# RAM.net
KiCad netlist of a schematic drawn in Altium Designer
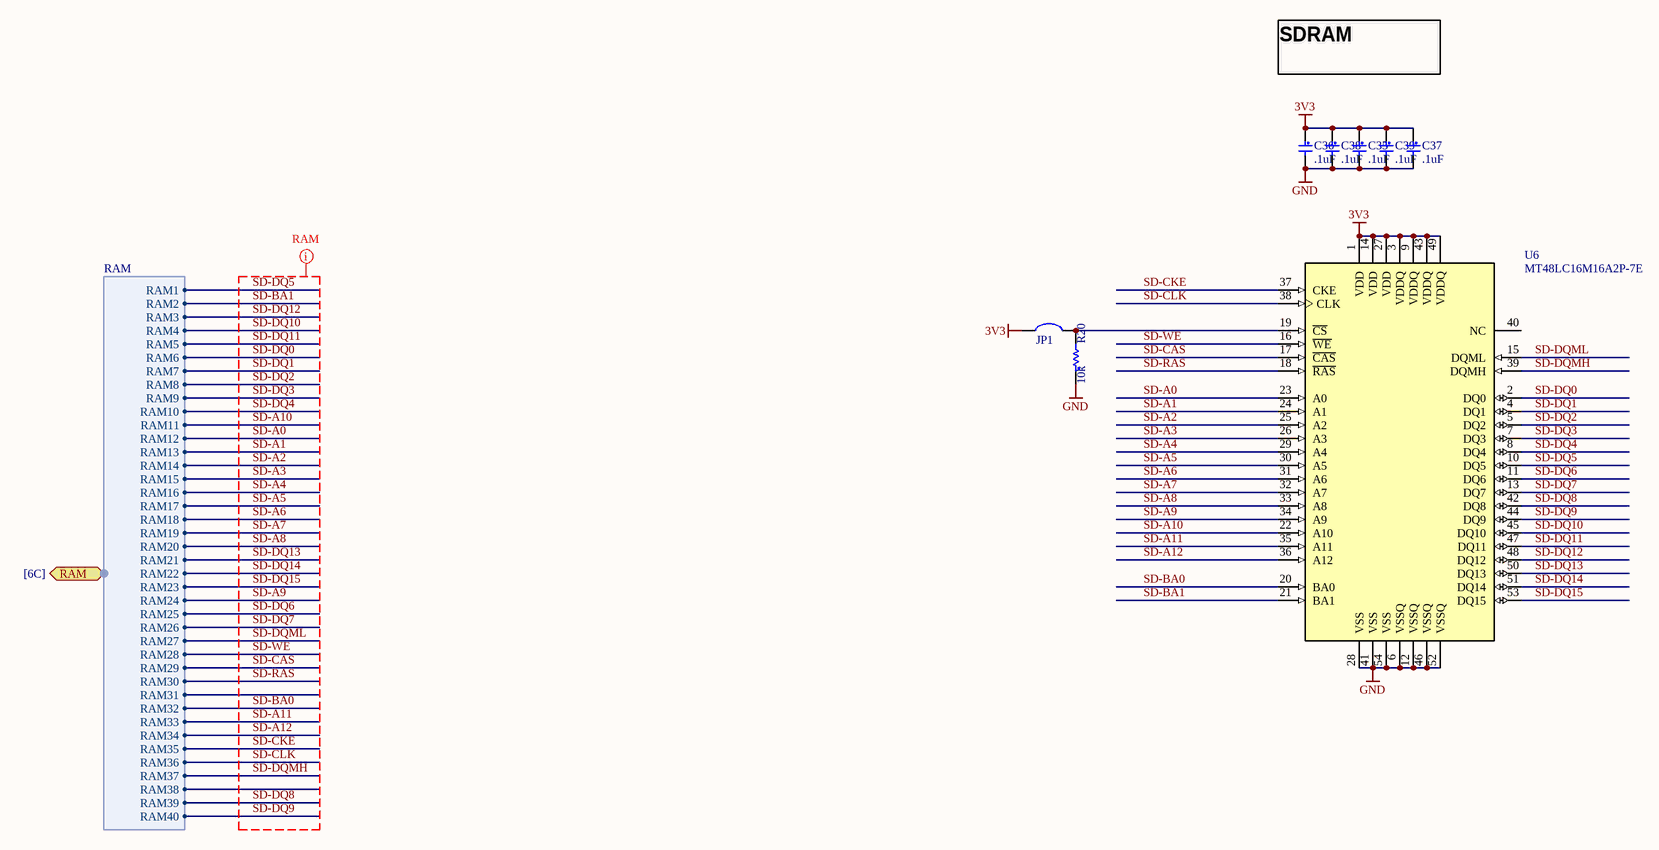
[diagram p0: RAM.SchDoc]

(export (version "E")
  (design (tool "Eeschema 10.0.6"))
  (components
    (comp (ref "C35")
      (value ".1uF")
      (description "CAP CER 0.1UF 25V Y5V 0603")
      (fields
        (field (name "MANUFACTURER") "Samsung Electro-Mechanics America, Inc")
        (field (name "MANUFACTURER PART NUMBER") "CL10F104ZA8NNNC")
      )
      (libsource (lib "mCapacitors") (part "C0603 - CL10F104ZA8NNNC"))
    )
    (comp (ref "C36")
      (value ".1uF")
      (description "CAP CER 0.1UF 25V Y5V 0603")
      (fields
        (field (name "MANUFACTURER") "Samsung Electro-Mechanics America, Inc")
        (field (name "MANUFACTURER PART NUMBER") "CL10F104ZA8NNNC")
      )
      (libsource (lib "mCapacitors") (part "C0603 - CL10F104ZA8NNNC"))
    )
    (comp (ref "C37")
      (value ".1uF")
      (description "CAP CER 0.1UF 25V Y5V 0603")
      (fields
        (field (name "MANUFACTURER") "Samsung Electro-Mechanics America, Inc")
        (field (name "MANUFACTURER PART NUMBER") "CL10F104ZA8NNNC")
      )
      (libsource (lib "mCapacitors") (part "C0603 - CL10F104ZA8NNNC"))
    )
    (comp (ref "C38")
      (value ".1uF")
      (description "CAP CER 0.1UF 25V Y5V 0603")
      (fields
        (field (name "MANUFACTURER") "Samsung Electro-Mechanics America, Inc")
        (field (name "MANUFACTURER PART NUMBER") "CL10F104ZA8NNNC")
      )
      (libsource (lib "mCapacitors") (part "C0603 - CL10F104ZA8NNNC"))
    )
    (comp (ref "C39")
      (value ".1uF")
      (description "CAP CER 0.1UF 25V Y5V 0603")
      (fields
        (field (name "MANUFACTURER") "Samsung Electro-Mechanics America, Inc")
        (field (name "MANUFACTURER PART NUMBER") "CL10F104ZA8NNNC")
      )
      (libsource (lib "mCapacitors") (part "C0603 - CL10F104ZA8NNNC"))
    )
    (comp (ref "JP1")
      (value "Solder Jumper")
      (footprint "SOLDER_JUMPER")
      (description "Solder/Configuration Jumper")
      (fields (field (name "MANUFACTURER") "n/a"))
      (libsource (lib "mConnector") (part "Solder Jumper"))
    )
    (comp (ref "R20")
      (value "10k")
      (footprint "mRCL:R0603")
      (description "10k Thick Film Resistors - SMD 1/10watt 10Kohms 1%")
      (fields
        (field (name "MANUFACTURER") "Vishay Dale")
        (field (name "MANUFACTURER PART NUMBER") "CRCW060310K0FKEA")
      )
      (libsource (lib "mResistors") (part "R0603 - CRCW060310K0FKEA"))
    )
    (comp (ref "U6")
      (value "MT48LC16M16A2P-7E")
      (footprint "mic:TSOP2-54_L")
      (description "256Mb Synchronous High-Speed CMOS DRAM, 16Mb x 16Bit x 4 Banks, 54-Pin TSOP Pb-free, Commercial")
      (fields
        (field (name "MANUFACTURER") "MICRON")
        (field (name "MANUFACTURER PART NUMBER") "MT48LC16M16A2P-7E IT:G")
      )
      (libsource (lib "mIC") (part "SDRAM - MT48LC16M16A2P-7E"))
    )
  )
  (nets
    (net (code "2") (name "/SD-A0") (class "Default")
      (node (ref "U6") (pin "23") (pinfunction "A0_23") (pintype "input"))
    )
    (net (code "3") (name "/SD-A1") (class "Default")
      (node (ref "U6") (pin "24") (pinfunction "A1_24") (pintype "input"))
    )
    (net (code "4") (name "/SD-A2") (class "Default")
      (node (ref "U6") (pin "25") (pinfunction "A2_25") (pintype "input"))
    )
    (net (code "5") (name "/SD-A3") (class "Default")
      (node (ref "U6") (pin "26") (pinfunction "A3_26") (pintype "input"))
    )
    (net (code "6") (name "/SD-A4") (class "Default")
      (node (ref "U6") (pin "29") (pinfunction "A4_29") (pintype "input"))
    )
    (net (code "7") (name "/SD-A5") (class "Default")
      (node (ref "U6") (pin "30") (pinfunction "A5_30") (pintype "input"))
    )
    (net (code "8") (name "/SD-A6") (class "Default")
      (node (ref "U6") (pin "31") (pinfunction "A6_31") (pintype "input"))
    )
    (net (code "9") (name "/SD-A7") (class "Default")
      (node (ref "U6") (pin "32") (pinfunction "A7_32") (pintype "input"))
    )
    (net (code "10") (name "/SD-A8") (class "Default")
      (node (ref "U6") (pin "33") (pinfunction "A8_33") (pintype "input"))
    )
    (net (code "11") (name "/SD-A9") (class "Default")
      (node (ref "U6") (pin "34") (pinfunction "A9_34") (pintype "input"))
    )
    (net (code "12") (name "/SD-A10") (class "Default")
      (node (ref "U6") (pin "22") (pinfunction "A10_22") (pintype "input"))
    )
    (net (code "13") (name "/SD-A11") (class "Default")
      (node (ref "U6") (pin "35") (pinfunction "A11_35") (pintype "input"))
    )
    (net (code "14") (name "/SD-A12") (class "Default")
      (node (ref "U6") (pin "36") (pinfunction "A12_36") (pintype "input"))
    )
    (net (code "15") (name "/SD-BA0") (class "Default")
      (node (ref "U6") (pin "20") (pinfunction "BA0_20") (pintype "input"))
    )
    (net (code "16") (name "/SD-BA1") (class "Default")
      (node (ref "U6") (pin "21") (pinfunction "BA1_21") (pintype "input"))
    )
    (net (code "17") (name "/SD-CAS") (class "Default")
      (node (ref "U6") (pin "17") (pinfunction "~{CAS}_17") (pintype "input"))
    )
    (net (code "18") (name "/SD-CKE") (class "Default")
      (node (ref "U6") (pin "37") (pinfunction "CKE_37") (pintype "input"))
    )
    (net (code "19") (name "/SD-CLK") (class "Default")
      (node (ref "U6") (pin "38") (pinfunction "CLK_38") (pintype "input"))
    )
    (net (code "20") (name "/SD-DQ0") (class "Default")
      (node (ref "U6") (pin "2") (pinfunction "DQ0_2") (pintype "bidirectional"))
    )
    (net (code "21") (name "/SD-DQ1") (class "Default")
      (node (ref "U6") (pin "4") (pinfunction "DQ1_4") (pintype "bidirectional"))
    )
    (net (code "22") (name "/SD-DQ2") (class "Default")
      (node (ref "U6") (pin "5") (pinfunction "DQ2_5") (pintype "bidirectional"))
    )
    (net (code "23") (name "/SD-DQ3") (class "Default")
      (node (ref "U6") (pin "7") (pinfunction "DQ3_7") (pintype "bidirectional"))
    )
    (net (code "24") (name "/SD-DQ4") (class "Default")
      (node (ref "U6") (pin "8") (pinfunction "DQ4_8") (pintype "bidirectional"))
    )
    (net (code "25") (name "/SD-DQ5") (class "Default")
      (node (ref "U6") (pin "10") (pinfunction "DQ5_10") (pintype "bidirectional"))
    )
    (net (code "26") (name "/SD-DQ6") (class "Default")
      (node (ref "U6") (pin "11") (pinfunction "DQ6_11") (pintype "bidirectional"))
    )
    (net (code "27") (name "/SD-DQ7") (class "Default")
      (node (ref "U6") (pin "13") (pinfunction "DQ7_13") (pintype "bidirectional"))
    )
    (net (code "28") (name "/SD-DQ8") (class "Default")
      (node (ref "U6") (pin "42") (pinfunction "DQ8_42") (pintype "bidirectional"))
    )
    (net (code "29") (name "/SD-DQ9") (class "Default")
      (node (ref "U6") (pin "44") (pinfunction "DQ9_44") (pintype "bidirectional"))
    )
    (net (code "30") (name "/SD-DQ10") (class "Default")
      (node (ref "U6") (pin "45") (pinfunction "DQ10_45") (pintype "bidirectional"))
    )
    (net (code "31") (name "/SD-DQ11") (class "Default")
      (node (ref "U6") (pin "47") (pinfunction "DQ11_47") (pintype "bidirectional"))
    )
    (net (code "32") (name "/SD-DQ12") (class "Default")
      (node (ref "U6") (pin "48") (pinfunction "DQ12_48") (pintype "bidirectional"))
    )
    (net (code "33") (name "/SD-DQ13") (class "Default")
      (node (ref "U6") (pin "50") (pinfunction "DQ13_50") (pintype "bidirectional"))
    )
    (net (code "34") (name "/SD-DQ14") (class "Default")
      (node (ref "U6") (pin "51") (pinfunction "DQ14_51") (pintype "bidirectional"))
    )
    (net (code "35") (name "/SD-DQ15") (class "Default")
      (node (ref "U6") (pin "53") (pinfunction "DQ15_53") (pintype "bidirectional"))
    )
    (net (code "36") (name "/SD-DQMH") (class "Default")
      (node (ref "U6") (pin "39") (pinfunction "DQMH_39") (pintype "input"))
    )
    (net (code "37") (name "/SD-DQML") (class "Default")
      (node (ref "U6") (pin "15") (pinfunction "DQML_15") (pintype "input"))
    )
    (net (code "38") (name "/SD-RAS") (class "Default")
      (node (ref "U6") (pin "18") (pinfunction "~{RAS}_18") (pintype "input"))
    )
    (net (code "39") (name "/SD-WE") (class "Default")
      (node (ref "U6") (pin "16") (pinfunction "~{WE}_16") (pintype "input"))
    )
    (net (code "41") (name "3V3") (class "Default")
      (node (ref "C35") (pin "1") (pinfunction "1_1") (pintype "passive"))
      (node (ref "C36") (pin "1") (pinfunction "1_1") (pintype "passive"))
      (node (ref "C37") (pin "1") (pinfunction "1_1") (pintype "passive"))
      (node (ref "C38") (pin "1") (pinfunction "1_1") (pintype "passive"))
      (node (ref "C39") (pin "1") (pinfunction "1_1") (pintype "passive"))
      (node (ref "JP1") (pin "1") (pinfunction "1_1") (pintype "passive"))
      (node (ref "U6") (pin "1") (pinfunction "VDD_1") (pintype "power_in"))
      (node (ref "U6") (pin "14") (pinfunction "VDD_14") (pintype "power_in"))
      (node (ref "U6") (pin "27") (pinfunction "VDD_27") (pintype "power_in"))
      (node (ref "U6") (pin "3") (pinfunction "VDDQ_3") (pintype "power_in"))
      (node (ref "U6") (pin "43") (pinfunction "VDDQ_43") (pintype "power_in"))
      (node (ref "U6") (pin "49") (pinfunction "VDDQ_49") (pintype "power_in"))
      (node (ref "U6") (pin "9") (pinfunction "VDDQ_9") (pintype "power_in"))
    )
    (net (code "42") (name "GND") (class "Default")
      (node (ref "C35") (pin "2") (pinfunction "2_2") (pintype "passive"))
      (node (ref "C36") (pin "2") (pinfunction "2_2") (pintype "passive"))
      (node (ref "C37") (pin "2") (pinfunction "2_2") (pintype "passive"))
      (node (ref "C38") (pin "2") (pinfunction "2_2") (pintype "passive"))
      (node (ref "C39") (pin "2") (pinfunction "2_2") (pintype "passive"))
      (node (ref "R20") (pin "1") (pinfunction "1_1") (pintype "passive"))
      (node (ref "U6") (pin "12") (pinfunction "VSSQ_12") (pintype "power_in"))
      (node (ref "U6") (pin "28") (pinfunction "VSS_28") (pintype "power_in"))
      (node (ref "U6") (pin "41") (pinfunction "VSS_41") (pintype "power_in"))
      (node (ref "U6") (pin "46") (pinfunction "VSSQ_46") (pintype "power_in"))
      (node (ref "U6") (pin "52") (pinfunction "VSSQ_52") (pintype "power_in"))
      (node (ref "U6") (pin "54") (pinfunction "VSS_54") (pintype "power_in"))
      (node (ref "U6") (pin "6") (pinfunction "VSSQ_6") (pintype "power_in"))
    )
    (net (code "43") (name "Net-(U6-~{CS})") (class "Default")
      (node (ref "JP1") (pin "2") (pinfunction "2_2") (pintype "passive"))
      (node (ref "R20") (pin "2") (pinfunction "2_2") (pintype "passive"))
      (node (ref "U6") (pin "19") (pinfunction "~{CS}_19") (pintype "input"))
    )
    (net (code "44") (name "unconnected-(U6-NC-Pad40)") (class "Default")
      (node (ref "U6") (pin "40") (pinfunction "NC_40") (pintype "passive"))
    )
  )
)
